# ChipHeadBang.net
KiCad netlist of a schematic drawn in EAGLE
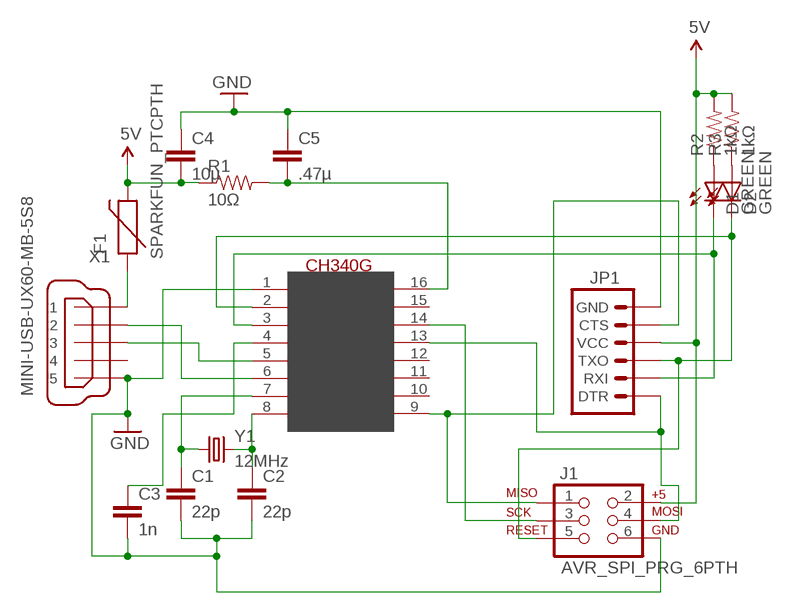
[diagram p0: schematic, sheet 1]

(export (version "E")
  (design (tool "Eeschema 10.0.6"))
  (components
    (comp (ref "C1")
      (value "22p")
      (footprint "eagle-import:0603-CAP")
      (libsource (lib "eagle-import") (part "CAP0603-CAP"))
    )
    (comp (ref "C2")
      (value "22p")
      (footprint "eagle-import:0603-CAP")
      (libsource (lib "eagle-import") (part "CAP0603-CAP"))
    )
    (comp (ref "C3")
      (value "1n")
      (footprint "eagle-import:0603-CAP")
      (libsource (lib "eagle-import") (part "CAP0603-CAP"))
    )
    (comp (ref "C4")
      (value "10µ")
      (footprint "eagle-import:0805")
      (libsource (lib "eagle-import") (part "CAP0805"))
    )
    (comp (ref "C5")
      (value ".47µ")
      (footprint "eagle-import:0805")
      (libsource (lib "eagle-import") (part "CAP0805"))
    )
    (comp (ref "D1")
      (value "GREEN")
      (footprint "eagle-import:LED-1206")
      (libsource (lib "eagle-import") (part "LED-GREENLARGE"))
    )
    (comp (ref "D2")
      (value "GREEN")
      (footprint "eagle-import:LED-1206")
      (libsource (lib "eagle-import") (part "LED-GREENLARGE"))
    )
    (comp (ref "F1")
      (value "SPARKFUN_PTCPTH")
      (footprint "eagle-import:SPARKFUN_PTC")
      (libsource (lib "eagle-import") (part "SPARKFUN_PTCPTH"))
    )
    (comp (ref "J1")
      (value "AVR_SPI_PRG_6PTH")
      (footprint "eagle-import:2X3")
      (libsource (lib "eagle-import") (part "AVR_SPI_PRG_6PTH"))
    )
    (comp (ref "JP1")
      (value "ARDUINO_SERIAL_PROGRAMPTH")
      (footprint "eagle-import:1X06")
      (libsource (lib "eagle-import") (part "ARDUINO_SERIAL_PROGRAMPTH"))
    )
    (comp (ref "R1")
      (value "10Ω")
      (footprint "eagle-import:0603-RES")
      (libsource (lib "eagle-import") (part "RESISTOR0603-RES"))
    )
    (comp (ref "R2")
      (value "1kΩ")
      (footprint "eagle-import:0603-RES")
      (libsource (lib "eagle-import") (part "RESISTOR0603-RES"))
    )
    (comp (ref "R3")
      (value "1kΩ")
      (footprint "eagle-import:0603-RES")
      (libsource (lib "eagle-import") (part "RESISTOR0603-RES"))
    )
    (comp (ref "U$1")
      (value "CH340G")
      (footprint "eagle-import:SOIC16")
      (libsource (lib "eagle-import") (part "CH340G"))
    )
    (comp (ref "X1")
      (value "MINI-USB-UX60-MB-5S8")
      (footprint "eagle-import:UX60-MB-5S8")
      (libsource (lib "eagle-import") (part "MINI-USB-UX60-MB-5S8"))
    )
    (comp (ref "Y1")
      (value "12MHz")
      (footprint "eagle-import:SPARKFUN_HC49US")
      (libsource (lib "eagle-import") (part "SPARKFUN_CRYSTALHC49US"))
    )
  )
  (nets
    (net (code "1") (name "5V") (class "Default")
      (node (ref "C4") (pin "2") (pinfunction "2_2") (pintype "passive"))
      (node (ref "F1") (pin "P$2") (pinfunction "2_P$2") (pintype "bidirectional"))
      (node (ref "J1") (pin "2") (pinfunction "2_2") (pintype "passive"))
      (node (ref "JP1") (pin "4") (pinfunction "VCC_4") (pintype "passive"))
      (node (ref "R1") (pin "1") (pinfunction "1_1") (pintype "passive"))
      (node (ref "R2") (pin "2") (pinfunction "2_2") (pintype "passive"))
      (node (ref "R3") (pin "2") (pinfunction "2_2") (pintype "passive"))
    )
    (net (code "2") (name "GND") (class "Default")
      (node (ref "C1") (pin "2") (pinfunction "2_2") (pintype "passive"))
      (node (ref "C2") (pin "2") (pinfunction "2_2") (pintype "passive"))
      (node (ref "C3") (pin "2") (pinfunction "2_2") (pintype "passive"))
      (node (ref "C4") (pin "1") (pinfunction "1_1") (pintype "passive"))
      (node (ref "C5") (pin "1") (pinfunction "1_1") (pintype "passive"))
      (node (ref "J1") (pin "6") (pinfunction "6_6") (pintype "passive"))
      (node (ref "JP1") (pin "6") (pinfunction "GND_6") (pintype "passive"))
      (node (ref "U$1") (pin "1") (pinfunction "GND_1") (pintype "bidirectional"))
      (node (ref "X1") (pin "5") (pinfunction "5_5") (pintype "input"))
    )
    (net (code "3") (name "Net-(D1-PadA)") (class "Default")
      (node (ref "D1") (pin "A") (pinfunction "A_A") (pintype "passive"))
      (node (ref "R2") (pin "1") (pinfunction "1_1") (pintype "passive"))
    )
    (net (code "4") (name "Net-(D2-PadA)") (class "Default")
      (node (ref "D2") (pin "A") (pinfunction "A_A") (pintype "passive"))
      (node (ref "R3") (pin "1") (pinfunction "1_1") (pintype "passive"))
    )
    (net (code "5") (name "Net-(F1-1)") (class "Default")
      (node (ref "F1") (pin "P$1") (pinfunction "1_P$1") (pintype "bidirectional"))
      (node (ref "X1") (pin "1") (pinfunction "1_1") (pintype "input"))
    )
    (net (code "6") (name "Net-(JP1-CTS)") (class "Default")
      (node (ref "J1") (pin "1") (pinfunction "1_1") (pintype "passive"))
      (node (ref "JP1") (pin "5") (pinfunction "CTS_5") (pintype "passive"))
      (node (ref "U$1") (pin "9") (pinfunction "CTS_9") (pintype "bidirectional"))
    )
    (net (code "7") (name "Net-(JP1-DTR)") (class "Default")
      (node (ref "J1") (pin "4") (pinfunction "4_4") (pintype "passive"))
      (node (ref "JP1") (pin "1") (pinfunction "DTR_1") (pintype "passive"))
      (node (ref "U$1") (pin "13") (pinfunction "DTR_13") (pintype "bidirectional"))
    )
    (net (code "8") (name "Net-(JP1-RXI)") (class "Default")
      (node (ref "D1") (pin "C") (pinfunction "C_C") (pintype "passive"))
      (node (ref "JP1") (pin "2") (pinfunction "RXI_2") (pintype "passive"))
      (node (ref "U$1") (pin "3") (pinfunction "RX_3") (pintype "bidirectional"))
    )
    (net (code "9") (name "Net-(JP1-TXO)") (class "Default")
      (node (ref "D2") (pin "C") (pinfunction "C_C") (pintype "passive"))
      (node (ref "J1") (pin "5") (pinfunction "5_5") (pintype "passive"))
      (node (ref "JP1") (pin "3") (pinfunction "TXO_3") (pintype "passive"))
      (node (ref "U$1") (pin "2") (pinfunction "TX_2") (pintype "bidirectional"))
    )
    (net (code "10") (name "Net-(U$1-D+)") (class "Default")
      (node (ref "U$1") (pin "5") (pinfunction "D+_5") (pintype "bidirectional"))
      (node (ref "X1") (pin "3") (pinfunction "3_3") (pintype "input"))
    )
    (net (code "11") (name "Net-(U$1-D-)") (class "Default")
      (node (ref "U$1") (pin "6") (pinfunction "D-_6") (pintype "bidirectional"))
      (node (ref "X1") (pin "2") (pinfunction "2_2") (pintype "input"))
    )
    (net (code "12") (name "Net-(U$1-RTS)") (class "Default")
      (node (ref "J1") (pin "3") (pinfunction "3_3") (pintype "passive"))
      (node (ref "U$1") (pin "14") (pinfunction "RTS_14") (pintype "bidirectional"))
    )
    (net (code "13") (name "Net-(U$1-V3)") (class "Default")
      (node (ref "C3") (pin "1") (pinfunction "1_1") (pintype "passive"))
      (node (ref "U$1") (pin "4") (pinfunction "V3_4") (pintype "bidirectional"))
    )
    (net (code "14") (name "Net-(U$1-VCC)") (class "Default")
      (node (ref "C5") (pin "2") (pinfunction "2_2") (pintype "passive"))
      (node (ref "R1") (pin "2") (pinfunction "2_2") (pintype "passive"))
      (node (ref "U$1") (pin "16") (pinfunction "VCC_16") (pintype "bidirectional"))
    )
    (net (code "15") (name "Net-(U$1-XI)") (class "Default")
      (node (ref "C1") (pin "1") (pinfunction "1_1") (pintype "passive"))
      (node (ref "U$1") (pin "7") (pinfunction "XI_7") (pintype "bidirectional"))
      (node (ref "Y1") (pin "1") (pinfunction "1_1") (pintype "passive"))
    )
    (net (code "16") (name "Net-(U$1-XO)") (class "Default")
      (node (ref "C2") (pin "1") (pinfunction "1_1") (pintype "passive"))
      (node (ref "U$1") (pin "8") (pinfunction "XO_8") (pintype "bidirectional"))
      (node (ref "Y1") (pin "2") (pinfunction "2_2") (pintype "passive"))
    )
    (net (code "17") (name "unconnected-(U$1-DCD-Pad12)") (class "Default")
      (node (ref "U$1") (pin "12") (pinfunction "DCD_12") (pintype "bidirectional"))
    )
    (net (code "18") (name "unconnected-(U$1-DSR-Pad10)") (class "Default")
      (node (ref "U$1") (pin "10") (pinfunction "DSR_10") (pintype "bidirectional"))
    )
    (net (code "19") (name "unconnected-(U$1-RI-Pad11)") (class "Default")
      (node (ref "U$1") (pin "11") (pinfunction "RI_11") (pintype "bidirectional"))
    )
    (net (code "20") (name "unconnected-(U$1-RS232-Pad15)") (class "Default")
      (node (ref "U$1") (pin "15") (pinfunction "RS232_15") (pintype "bidirectional"))
    )
    (net (code "21") (name "unconnected-(X1-Pad4)") (class "Default")
      (node (ref "X1") (pin "4") (pinfunction "4_4") (pintype "input"))
    )
  )
)
